# relay_board.net
KiCad netlist of a schematic drawn in EAGLE
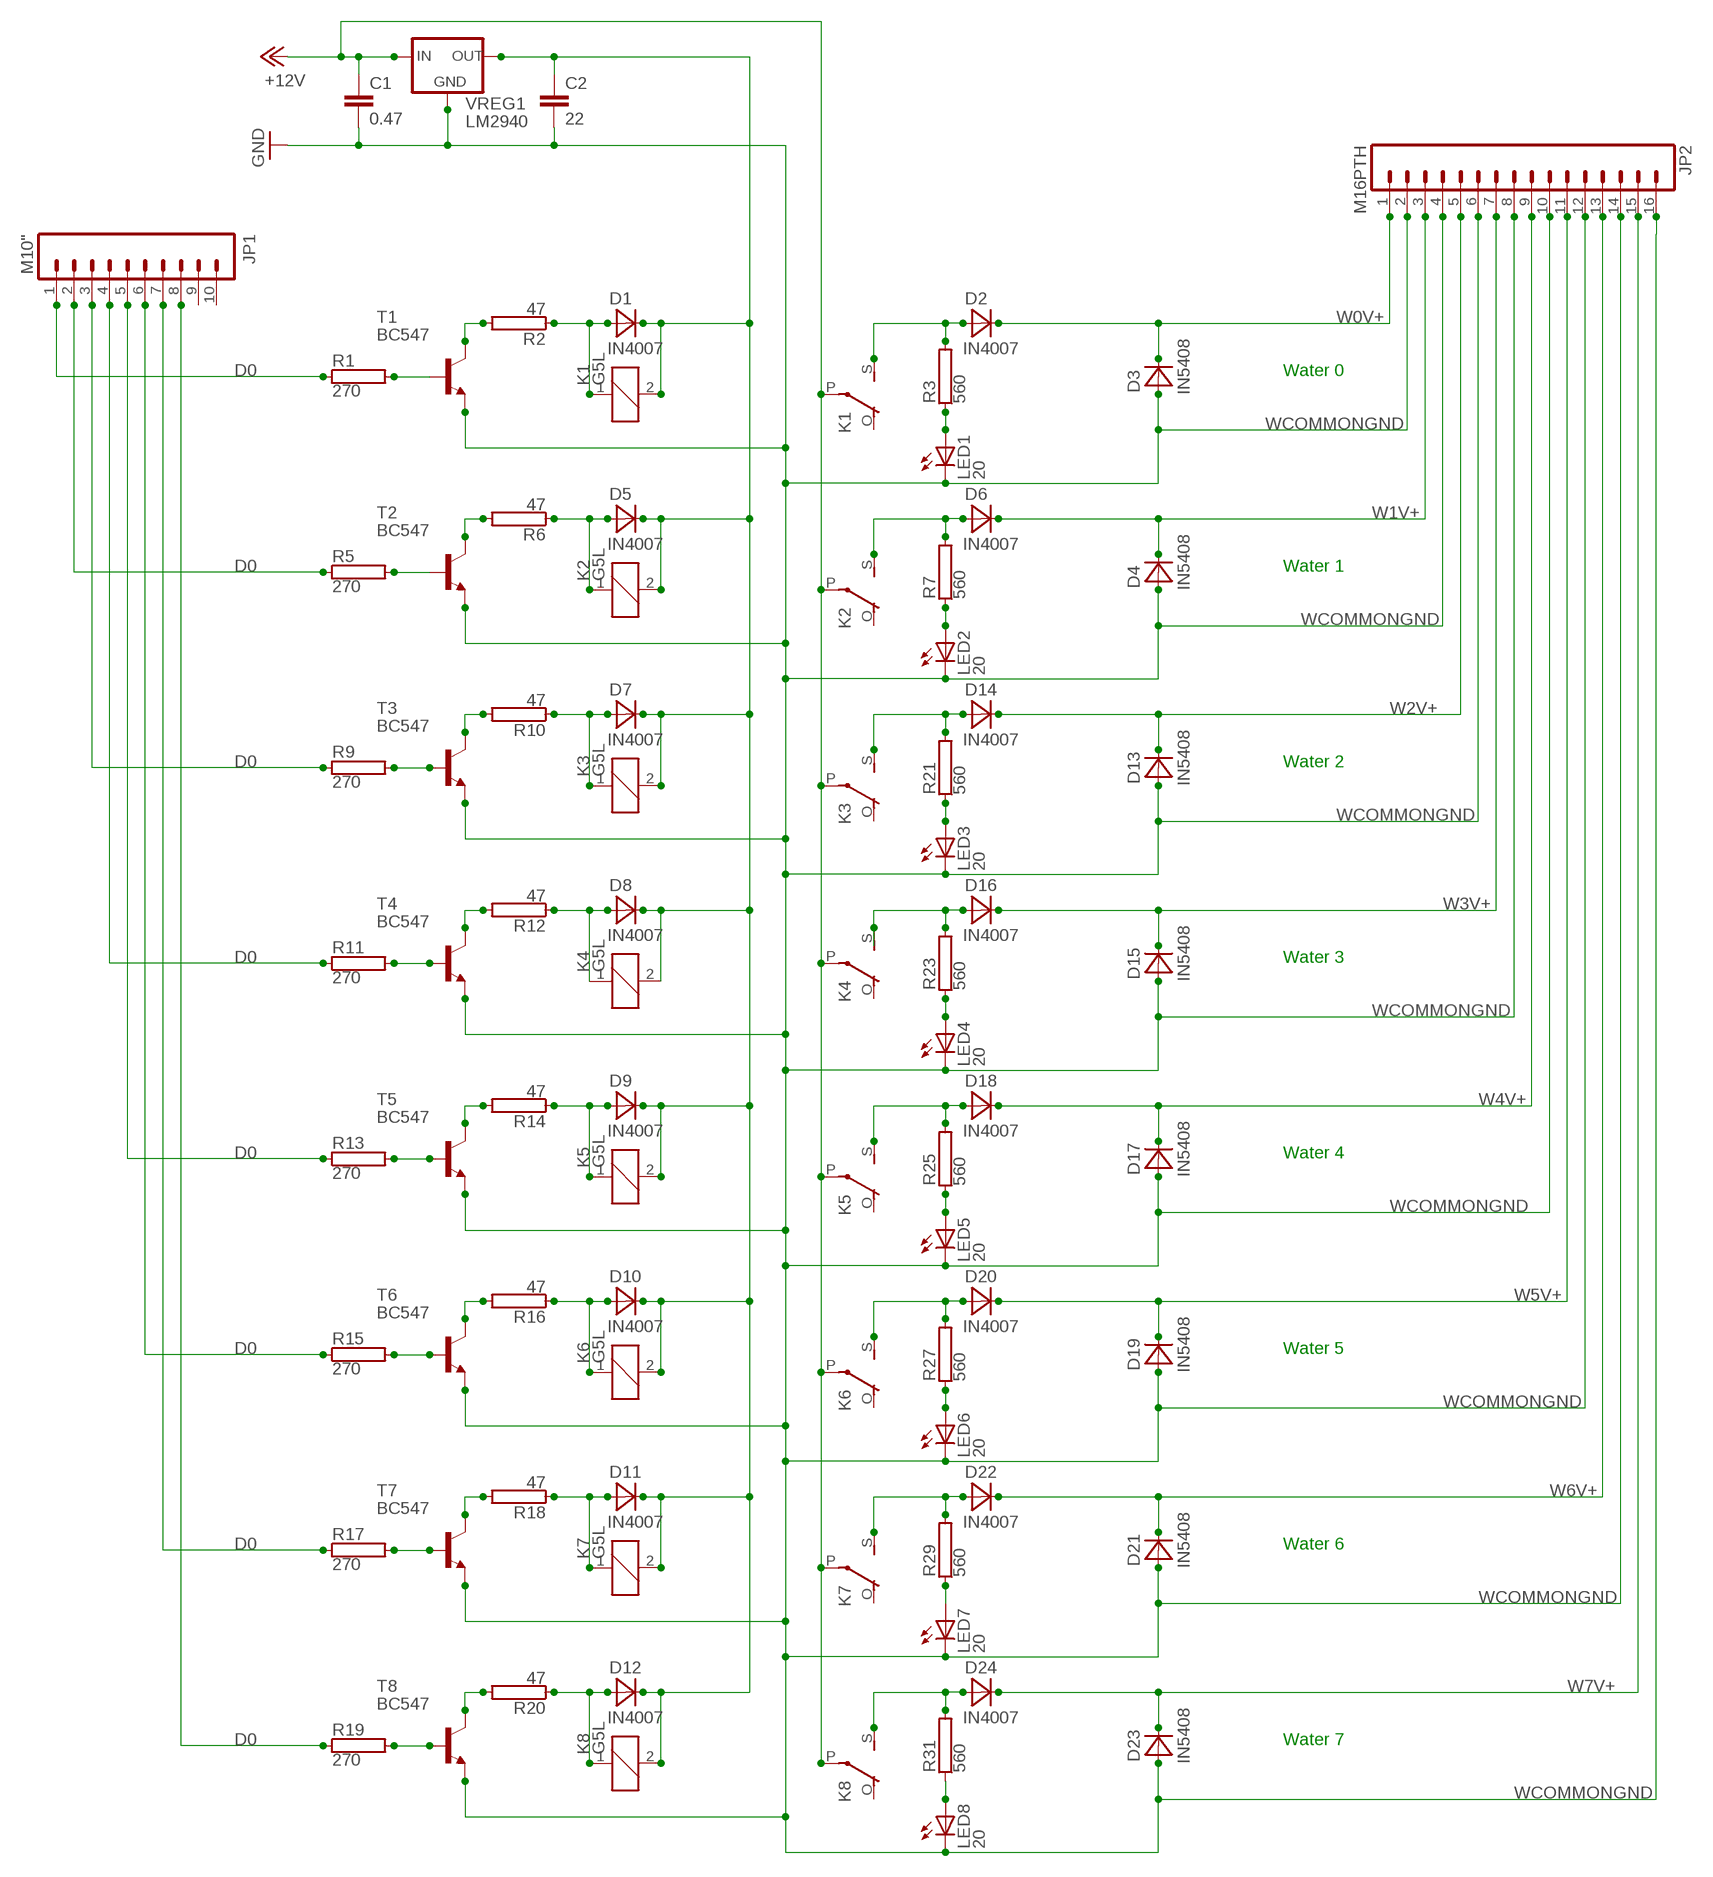
[diagram p0: schematic, sheet 1]

(export (version "E")
  (design (tool "Eeschema 10.0.6"))
  (components
    (comp (ref "C1")
      (value "0.47")
      (footprint "eagle-import:C2.5-3")
      (libsource (lib "eagle-import") (part "C2,5-3"))
    )
    (comp (ref "C2")
      (value "22")
      (footprint "eagle-import:C2.5-3")
      (libsource (lib "eagle-import") (part "C2,5-3"))
    )
    (comp (ref "D1")
      (value "IN4007")
      (footprint "eagle-import:DO41-10")
      (libsource (lib "eagle-import") (part "IN4007"))
    )
    (comp (ref "D2")
      (value "IN4007")
      (footprint "eagle-import:DO41-10")
      (libsource (lib "eagle-import") (part "IN4007"))
    )
    (comp (ref "D3")
      (value "IN5408")
      (footprint "eagle-import:DO41-10")
      (libsource (lib "eagle-import") (part "IN5408"))
    )
    (comp (ref "D4")
      (value "IN5408")
      (footprint "eagle-import:DO41-10")
      (libsource (lib "eagle-import") (part "IN5408"))
    )
    (comp (ref "D5")
      (value "IN4007")
      (footprint "eagle-import:DO41-10")
      (libsource (lib "eagle-import") (part "IN4007"))
    )
    (comp (ref "D6")
      (value "IN4007")
      (footprint "eagle-import:DO41-10")
      (libsource (lib "eagle-import") (part "IN4007"))
    )
    (comp (ref "D7")
      (value "IN4007")
      (footprint "eagle-import:DO41-10")
      (libsource (lib "eagle-import") (part "IN4007"))
    )
    (comp (ref "D8")
      (value "IN4007")
      (footprint "eagle-import:DO41-10")
      (libsource (lib "eagle-import") (part "IN4007"))
    )
    (comp (ref "D9")
      (value "IN4007")
      (footprint "eagle-import:DO41-10")
      (libsource (lib "eagle-import") (part "IN4007"))
    )
    (comp (ref "D10")
      (value "IN4007")
      (footprint "eagle-import:DO41-10")
      (libsource (lib "eagle-import") (part "IN4007"))
    )
    (comp (ref "D11")
      (value "IN4007")
      (footprint "eagle-import:DO41-10")
      (libsource (lib "eagle-import") (part "IN4007"))
    )
    (comp (ref "D12")
      (value "IN4007")
      (footprint "eagle-import:DO41-10")
      (libsource (lib "eagle-import") (part "IN4007"))
    )
    (comp (ref "D13")
      (value "IN5408")
      (footprint "eagle-import:DO41-10")
      (libsource (lib "eagle-import") (part "IN5408"))
    )
    (comp (ref "D14")
      (value "IN4007")
      (footprint "eagle-import:DO41-10")
      (libsource (lib "eagle-import") (part "IN4007"))
    )
    (comp (ref "D15")
      (value "IN5408")
      (footprint "eagle-import:DO41-10")
      (libsource (lib "eagle-import") (part "IN5408"))
    )
    (comp (ref "D16")
      (value "IN4007")
      (footprint "eagle-import:DO41-10")
      (libsource (lib "eagle-import") (part "IN4007"))
    )
    (comp (ref "D17")
      (value "IN5408")
      (footprint "eagle-import:DO41-10")
      (libsource (lib "eagle-import") (part "IN5408"))
    )
    (comp (ref "D18")
      (value "IN4007")
      (footprint "eagle-import:DO41-10")
      (libsource (lib "eagle-import") (part "IN4007"))
    )
    (comp (ref "D19")
      (value "IN5408")
      (footprint "eagle-import:DO41-10")
      (libsource (lib "eagle-import") (part "IN5408"))
    )
    (comp (ref "D20")
      (value "IN4007")
      (footprint "eagle-import:DO41-10")
      (libsource (lib "eagle-import") (part "IN4007"))
    )
    (comp (ref "D21")
      (value "IN5408")
      (footprint "eagle-import:DO41-10")
      (libsource (lib "eagle-import") (part "IN5408"))
    )
    (comp (ref "D22")
      (value "IN4007")
      (footprint "eagle-import:DO41-10")
      (libsource (lib "eagle-import") (part "IN4007"))
    )
    (comp (ref "D23")
      (value "IN5408")
      (footprint "eagle-import:DO41-10")
      (libsource (lib "eagle-import") (part "IN5408"))
    )
    (comp (ref "D24")
      (value "IN4007")
      (footprint "eagle-import:DO41-10")
      (libsource (lib "eagle-import") (part "IN4007"))
    )
    (comp (ref "JP1")
      (value "M10\"")
      (footprint "eagle-import:1X10")
      (libsource (lib "eagle-import") (part "M10{dblquote}"))
    )
    (comp (ref "JP2")
      (value "M16PTH")
      (footprint "eagle-import:1X16")
      (libsource (lib "eagle-import") (part "M16PTH"))
    )
    (comp (ref "K1")
      (value "G5L")
      (footprint "eagle-import:G5LE")
      (libsource (lib "eagle-import") (part "G5L"))
    )
    (comp (ref "K2")
      (value "G5L")
      (footprint "eagle-import:G5LE")
      (libsource (lib "eagle-import") (part "G5L"))
    )
    (comp (ref "K3")
      (value "G5L")
      (footprint "eagle-import:G5LE")
      (libsource (lib "eagle-import") (part "G5L"))
    )
    (comp (ref "K4")
      (value "G5L")
      (footprint "eagle-import:G5LE")
      (libsource (lib "eagle-import") (part "G5L"))
    )
    (comp (ref "K5")
      (value "G5L")
      (footprint "eagle-import:G5LE")
      (libsource (lib "eagle-import") (part "G5L"))
    )
    (comp (ref "K6")
      (value "G5L")
      (footprint "eagle-import:G5LE")
      (libsource (lib "eagle-import") (part "G5L"))
    )
    (comp (ref "K7")
      (value "G5L")
      (footprint "eagle-import:G5LE")
      (libsource (lib "eagle-import") (part "G5L"))
    )
    (comp (ref "K8")
      (value "G5L")
      (footprint "eagle-import:G5LE")
      (libsource (lib "eagle-import") (part "G5L"))
    )
    (comp (ref "LED1")
      (value "20")
      (footprint "eagle-import:LED5MM")
      (libsource (lib "eagle-import") (part "LED5MM"))
    )
    (comp (ref "LED2")
      (value "20")
      (footprint "eagle-import:LED5MM")
      (libsource (lib "eagle-import") (part "LED5MM"))
    )
    (comp (ref "LED3")
      (value "20")
      (footprint "eagle-import:LED5MM")
      (libsource (lib "eagle-import") (part "LED5MM"))
    )
    (comp (ref "LED4")
      (value "20")
      (footprint "eagle-import:LED5MM")
      (libsource (lib "eagle-import") (part "LED5MM"))
    )
    (comp (ref "LED5")
      (value "20")
      (footprint "eagle-import:LED5MM")
      (libsource (lib "eagle-import") (part "LED5MM"))
    )
    (comp (ref "LED6")
      (value "20")
      (footprint "eagle-import:LED5MM")
      (libsource (lib "eagle-import") (part "LED5MM"))
    )
    (comp (ref "LED7")
      (value "20")
      (footprint "eagle-import:LED5MM")
      (libsource (lib "eagle-import") (part "LED5MM"))
    )
    (comp (ref "LED8")
      (value "20")
      (footprint "eagle-import:LED5MM")
      (libsource (lib "eagle-import") (part "LED5MM"))
    )
    (comp (ref "R1")
      (value "270")
      (footprint "eagle-import:AC01")
      (libsource (lib "eagle-import") (part "RAC01"))
    )
    (comp (ref "R2")
      (value "47")
      (footprint "eagle-import:AC01")
      (libsource (lib "eagle-import") (part "RAC01"))
    )
    (comp (ref "R3")
      (value "560")
      (footprint "eagle-import:AC01")
      (libsource (lib "eagle-import") (part "RAC01"))
    )
    (comp (ref "R5")
      (value "270")
      (footprint "eagle-import:AC01")
      (libsource (lib "eagle-import") (part "RAC01"))
    )
    (comp (ref "R6")
      (value "47")
      (footprint "eagle-import:AC01")
      (libsource (lib "eagle-import") (part "RAC01"))
    )
    (comp (ref "R7")
      (value "560")
      (footprint "eagle-import:AC01")
      (libsource (lib "eagle-import") (part "RAC01"))
    )
    (comp (ref "R9")
      (value "270")
      (footprint "eagle-import:AC01")
      (libsource (lib "eagle-import") (part "RAC01"))
    )
    (comp (ref "R10")
      (value "47")
      (footprint "eagle-import:AC01")
      (libsource (lib "eagle-import") (part "RAC01"))
    )
    (comp (ref "R11")
      (value "270")
      (footprint "eagle-import:AC01")
      (libsource (lib "eagle-import") (part "RAC01"))
    )
    (comp (ref "R12")
      (value "47")
      (footprint "eagle-import:AC01")
      (libsource (lib "eagle-import") (part "RAC01"))
    )
    (comp (ref "R13")
      (value "270")
      (footprint "eagle-import:AC01")
      (libsource (lib "eagle-import") (part "RAC01"))
    )
    (comp (ref "R14")
      (value "47")
      (footprint "eagle-import:AC01")
      (libsource (lib "eagle-import") (part "RAC01"))
    )
    (comp (ref "R15")
      (value "270")
      (footprint "eagle-import:AC01")
      (libsource (lib "eagle-import") (part "RAC01"))
    )
    (comp (ref "R16")
      (value "47")
      (footprint "eagle-import:AC01")
      (libsource (lib "eagle-import") (part "RAC01"))
    )
    (comp (ref "R17")
      (value "270")
      (footprint "eagle-import:AC01")
      (libsource (lib "eagle-import") (part "RAC01"))
    )
    (comp (ref "R18")
      (value "47")
      (footprint "eagle-import:AC01")
      (libsource (lib "eagle-import") (part "RAC01"))
    )
    (comp (ref "R19")
      (value "270")
      (footprint "eagle-import:AC01")
      (libsource (lib "eagle-import") (part "RAC01"))
    )
    (comp (ref "R20")
      (value "47")
      (footprint "eagle-import:AC01")
      (libsource (lib "eagle-import") (part "RAC01"))
    )
    (comp (ref "R21")
      (value "560")
      (footprint "eagle-import:AC01")
      (libsource (lib "eagle-import") (part "RAC01"))
    )
    (comp (ref "R23")
      (value "560")
      (footprint "eagle-import:AC01")
      (libsource (lib "eagle-import") (part "RAC01"))
    )
    (comp (ref "R25")
      (value "560")
      (footprint "eagle-import:AC01")
      (libsource (lib "eagle-import") (part "RAC01"))
    )
    (comp (ref "R27")
      (value "560")
      (footprint "eagle-import:AC01")
      (libsource (lib "eagle-import") (part "RAC01"))
    )
    (comp (ref "R29")
      (value "560")
      (footprint "eagle-import:AC01")
      (libsource (lib "eagle-import") (part "RAC01"))
    )
    (comp (ref "R31")
      (value "560")
      (footprint "eagle-import:AC01")
      (libsource (lib "eagle-import") (part "RAC01"))
    )
    (comp (ref "T1")
      (value "BC547")
      (footprint "eagle-import:TO92")
      (libsource (lib "eagle-import") (part "BC547"))
    )
    (comp (ref "T2")
      (value "BC547")
      (footprint "eagle-import:TO92")
      (libsource (lib "eagle-import") (part "BC547"))
    )
    (comp (ref "T3")
      (value "BC547")
      (footprint "eagle-import:TO92")
      (libsource (lib "eagle-import") (part "BC547"))
    )
    (comp (ref "T4")
      (value "BC547")
      (footprint "eagle-import:TO92")
      (libsource (lib "eagle-import") (part "BC547"))
    )
    (comp (ref "T5")
      (value "BC547")
      (footprint "eagle-import:TO92")
      (libsource (lib "eagle-import") (part "BC547"))
    )
    (comp (ref "T6")
      (value "BC547")
      (footprint "eagle-import:TO92")
      (libsource (lib "eagle-import") (part "BC547"))
    )
    (comp (ref "T7")
      (value "BC547")
      (footprint "eagle-import:TO92")
      (libsource (lib "eagle-import") (part "BC547"))
    )
    (comp (ref "T8")
      (value "BC547")
      (footprint "eagle-import:TO92")
      (libsource (lib "eagle-import") (part "BC547"))
    )
    (comp (ref "VREG1")
      (value "LM2940")
      (footprint "eagle-import:78XXL")
      (libsource (lib "eagle-import") (part "LM2940"))
    )
  )
  (nets
    (net (code "1") (name "+12V") (class "Default")
      (node (ref "C1") (pin "1") (pinfunction "1_1") (pintype "passive"))
      (node (ref "K1") (pin "P") (pinfunction "P_P") (pintype "passive"))
      (node (ref "K2") (pin "P") (pinfunction "P_P") (pintype "passive"))
      (node (ref "K3") (pin "P") (pinfunction "P_P") (pintype "passive"))
      (node (ref "K4") (pin "P") (pinfunction "P_P") (pintype "passive"))
      (node (ref "K5") (pin "P") (pinfunction "P_P") (pintype "passive"))
      (node (ref "K6") (pin "P") (pinfunction "P_P") (pintype "passive"))
      (node (ref "K7") (pin "P") (pinfunction "P_P") (pintype "passive"))
      (node (ref "K8") (pin "P") (pinfunction "P_P") (pintype "passive"))
      (node (ref "VREG1") (pin "IN") (pinfunction "IN_IN") (pintype "input"))
    )
    (net (code "2") (name "/D0") (class "Default")
      (node (ref "JP1") (pin "1") (pinfunction "1_1") (pintype "passive"))
      (node (ref "JP1") (pin "2") (pinfunction "2_2") (pintype "passive"))
      (node (ref "JP1") (pin "3") (pinfunction "3_3") (pintype "passive"))
      (node (ref "JP1") (pin "4") (pinfunction "4_4") (pintype "passive"))
      (node (ref "JP1") (pin "5") (pinfunction "5_5") (pintype "passive"))
      (node (ref "JP1") (pin "6") (pinfunction "6_6") (pintype "passive"))
      (node (ref "JP1") (pin "7") (pinfunction "7_7") (pintype "passive"))
      (node (ref "JP1") (pin "8") (pinfunction "8_8") (pintype "passive"))
      (node (ref "R1") (pin "1") (pinfunction "1_1") (pintype "passive"))
      (node (ref "R11") (pin "1") (pinfunction "1_1") (pintype "passive"))
      (node (ref "R13") (pin "1") (pinfunction "1_1") (pintype "passive"))
      (node (ref "R15") (pin "1") (pinfunction "1_1") (pintype "passive"))
      (node (ref "R17") (pin "1") (pinfunction "1_1") (pintype "passive"))
      (node (ref "R19") (pin "1") (pinfunction "1_1") (pintype "passive"))
      (node (ref "R5") (pin "1") (pinfunction "1_1") (pintype "passive"))
      (node (ref "R9") (pin "1") (pinfunction "1_1") (pintype "passive"))
    )
    (net (code "3") (name "/W0V+") (class "Default")
      (node (ref "D2") (pin "C") (pinfunction "C_C") (pintype "passive"))
      (node (ref "D3") (pin "C") (pinfunction "C_C") (pintype "passive"))
      (node (ref "JP2") (pin "1") (pinfunction "1_1") (pintype "passive"))
    )
    (net (code "4") (name "/W1V+") (class "Default")
      (node (ref "D4") (pin "C") (pinfunction "C_C") (pintype "passive"))
      (node (ref "D6") (pin "C") (pinfunction "C_C") (pintype "passive"))
      (node (ref "JP2") (pin "3") (pinfunction "3_3") (pintype "passive"))
    )
    (net (code "5") (name "/W2V+") (class "Default")
      (node (ref "D13") (pin "C") (pinfunction "C_C") (pintype "passive"))
      (node (ref "D14") (pin "C") (pinfunction "C_C") (pintype "passive"))
      (node (ref "JP2") (pin "5") (pinfunction "5_5") (pintype "passive"))
    )
    (net (code "6") (name "/W3V+") (class "Default")
      (node (ref "D15") (pin "C") (pinfunction "C_C") (pintype "passive"))
      (node (ref "D16") (pin "C") (pinfunction "C_C") (pintype "passive"))
      (node (ref "JP2") (pin "7") (pinfunction "7_7") (pintype "passive"))
    )
    (net (code "7") (name "/W4V+") (class "Default")
      (node (ref "D17") (pin "C") (pinfunction "C_C") (pintype "passive"))
      (node (ref "D18") (pin "C") (pinfunction "C_C") (pintype "passive"))
      (node (ref "JP2") (pin "9") (pinfunction "9_9") (pintype "passive"))
    )
    (net (code "8") (name "/W5V+") (class "Default")
      (node (ref "D19") (pin "C") (pinfunction "C_C") (pintype "passive"))
      (node (ref "D20") (pin "C") (pinfunction "C_C") (pintype "passive"))
      (node (ref "JP2") (pin "11") (pinfunction "11_11") (pintype "passive"))
    )
    (net (code "9") (name "/W6V+") (class "Default")
      (node (ref "D21") (pin "C") (pinfunction "C_C") (pintype "passive"))
      (node (ref "D22") (pin "C") (pinfunction "C_C") (pintype "passive"))
      (node (ref "JP2") (pin "13") (pinfunction "13_13") (pintype "passive"))
    )
    (net (code "10") (name "/W7V+") (class "Default")
      (node (ref "D23") (pin "C") (pinfunction "C_C") (pintype "passive"))
      (node (ref "D24") (pin "C") (pinfunction "C_C") (pintype "passive"))
      (node (ref "JP2") (pin "15") (pinfunction "15_15") (pintype "passive"))
    )
    (net (code "11") (name "GND") (class "Default")
      (node (ref "C1") (pin "2") (pinfunction "2_2") (pintype "passive"))
      (node (ref "C2") (pin "2") (pinfunction "2_2") (pintype "passive"))
      (node (ref "D13") (pin "A") (pinfunction "A_A") (pintype "passive"))
      (node (ref "D15") (pin "A") (pinfunction "A_A") (pintype "passive"))
      (node (ref "D17") (pin "A") (pinfunction "A_A") (pintype "passive"))
      (node (ref "D19") (pin "A") (pinfunction "A_A") (pintype "passive"))
      (node (ref "D21") (pin "A") (pinfunction "A_A") (pintype "passive"))
      (node (ref "D23") (pin "A") (pinfunction "A_A") (pintype "passive"))
      (node (ref "D3") (pin "A") (pinfunction "A_A") (pintype "passive"))
      (node (ref "D4") (pin "A") (pinfunction "A_A") (pintype "passive"))
      (node (ref "JP2") (pin "10") (pinfunction "10_10") (pintype "passive"))
      (node (ref "JP2") (pin "12") (pinfunction "12_12") (pintype "passive"))
      (node (ref "JP2") (pin "14") (pinfunction "14_14") (pintype "passive"))
      (node (ref "JP2") (pin "16") (pinfunction "16_16") (pintype "passive"))
      (node (ref "JP2") (pin "2") (pinfunction "2_2") (pintype "passive"))
      (node (ref "JP2") (pin "4") (pinfunction "4_4") (pintype "passive"))
      (node (ref "JP2") (pin "6") (pinfunction "6_6") (pintype "passive"))
      (node (ref "JP2") (pin "8") (pinfunction "8_8") (pintype "passive"))
      (node (ref "LED1") (pin "K") (pinfunction "C_K") (pintype "passive"))
      (node (ref "LED2") (pin "K") (pinfunction "C_K") (pintype "passive"))
      (node (ref "LED3") (pin "K") (pinfunction "C_K") (pintype "passive"))
      (node (ref "LED4") (pin "K") (pinfunction "C_K") (pintype "passive"))
      (node (ref "LED5") (pin "K") (pinfunction "C_K") (pintype "passive"))
      (node (ref "LED6") (pin "K") (pinfunction "C_K") (pintype "passive"))
      (node (ref "LED7") (pin "K") (pinfunction "C_K") (pintype "passive"))
      (node (ref "LED8") (pin "K") (pinfunction "C_K") (pintype "passive"))
      (node (ref "T1") (pin "1") (pinfunction "E_1") (pintype "passive"))
      (node (ref "T2") (pin "1") (pinfunction "E_1") (pintype "passive"))
      (node (ref "T3") (pin "1") (pinfunction "E_1") (pintype "passive"))
      (node (ref "T4") (pin "1") (pinfunction "E_1") (pintype "passive"))
      (node (ref "T5") (pin "1") (pinfunction "E_1") (pintype "passive"))
      (node (ref "T6") (pin "1") (pinfunction "E_1") (pintype "passive"))
      (node (ref "T7") (pin "1") (pinfunction "E_1") (pintype "passive"))
      (node (ref "T8") (pin "1") (pinfunction "E_1") (pintype "passive"))
      (node (ref "VREG1") (pin "GND") (pinfunction "GND_GND") (pintype "input"))
    )
    (net (code "12") (name "Net-(C2-Pad1)") (class "Default")
      (node (ref "C2") (pin "1") (pinfunction "1_1") (pintype "passive"))
      (node (ref "D1") (pin "C") (pinfunction "C_C") (pintype "passive"))
      (node (ref "D10") (pin "C") (pinfunction "C_C") (pintype "passive"))
      (node (ref "D11") (pin "C") (pinfunction "C_C") (pintype "passive"))
      (node (ref "D12") (pin "C") (pinfunction "C_C") (pintype "passive"))
      (node (ref "D5") (pin "C") (pinfunction "C_C") (pintype "passive"))
      (node (ref "D7") (pin "C") (pinfunction "C_C") (pintype "passive"))
      (node (ref "D8") (pin "C") (pinfunction "C_C") (pintype "passive"))
      (node (ref "D9") (pin "C") (pinfunction "C_C") (pintype "passive"))
      (node (ref "K1") (pin "2") (pinfunction "2_2") (pintype "passive"))
      (node (ref "K2") (pin "2") (pinfunction "2_2") (pintype "passive"))
      (node (ref "K3") (pin "2") (pinfunction "2_2") (pintype "passive"))
      (node (ref "K4") (pin "2") (pinfunction "2_2") (pintype "passive"))
      (node (ref "K5") (pin "2") (pinfunction "2_2") (pintype "passive"))
      (node (ref "K6") (pin "2") (pinfunction "2_2") (pintype "passive"))
      (node (ref "K7") (pin "2") (pinfunction "2_2") (pintype "passive"))
      (node (ref "K8") (pin "2") (pinfunction "2_2") (pintype "passive"))
      (node (ref "VREG1") (pin "OUT") (pinfunction "OUT_OUT") (pintype "passive"))
    )
    (net (code "13") (name "Net-(D1-PadA)") (class "Default")
      (node (ref "D1") (pin "A") (pinfunction "A_A") (pintype "passive"))
      (node (ref "K1") (pin "1") (pinfunction "1_1") (pintype "passive"))
      (node (ref "R2") (pin "1") (pinfunction "1_1") (pintype "passive"))
    )
    (net (code "14") (name "Net-(D2-PadA)") (class "Default")
      (node (ref "D2") (pin "A") (pinfunction "A_A") (pintype "passive"))
      (node (ref "K1") (pin "S") (pinfunction "S_S") (pintype "passive"))
      (node (ref "R3") (pin "2") (pinfunction "2_2") (pintype "passive"))
    )
    (net (code "15") (name "Net-(D5-PadA)") (class "Default")
      (node (ref "D5") (pin "A") (pinfunction "A_A") (pintype "passive"))
      (node (ref "K2") (pin "1") (pinfunction "1_1") (pintype "passive"))
      (node (ref "R6") (pin "1") (pinfunction "1_1") (pintype "passive"))
    )
    (net (code "16") (name "Net-(D6-PadA)") (class "Default")
      (node (ref "D6") (pin "A") (pinfunction "A_A") (pintype "passive"))
      (node (ref "K2") (pin "S") (pinfunction "S_S") (pintype "passive"))
      (node (ref "R7") (pin "2") (pinfunction "2_2") (pintype "passive"))
    )
    (net (code "17") (name "Net-(D7-PadA)") (class "Default")
      (node (ref "D7") (pin "A") (pinfunction "A_A") (pintype "passive"))
      (node (ref "K3") (pin "1") (pinfunction "1_1") (pintype "passive"))
      (node (ref "R10") (pin "1") (pinfunction "1_1") (pintype "passive"))
    )
    (net (code "18") (name "Net-(D8-PadA)") (class "Default")
      (node (ref "D8") (pin "A") (pinfunction "A_A") (pintype "passive"))
      (node (ref "K4") (pin "1") (pinfunction "1_1") (pintype "passive"))
      (node (ref "R12") (pin "1") (pinfunction "1_1") (pintype "passive"))
    )
    (net (code "19") (name "Net-(D9-PadA)") (class "Default")
      (node (ref "D9") (pin "A") (pinfunction "A_A") (pintype "passive"))
      (node (ref "K5") (pin "1") (pinfunction "1_1") (pintype "passive"))
      (node (ref "R14") (pin "1") (pinfunction "1_1") (pintype "passive"))
    )
    (net (code "20") (name "Net-(D10-PadA)") (class "Default")
      (node (ref "D10") (pin "A") (pinfunction "A_A") (pintype "passive"))
      (node (ref "K6") (pin "1") (pinfunction "1_1") (pintype "passive"))
      (node (ref "R16") (pin "1") (pinfunction "1_1") (pintype "passive"))
    )
    (net (code "21") (name "Net-(D11-PadA)") (class "Default")
      (node (ref "D11") (pin "A") (pinfunction "A_A") (pintype "passive"))
      (node (ref "K7") (pin "1") (pinfunction "1_1") (pintype "passive"))
      (node (ref "R18") (pin "1") (pinfunction "1_1") (pintype "passive"))
    )
    (net (code "22") (name "Net-(D12-PadA)") (class "Default")
      (node (ref "D12") (pin "A") (pinfunction "A_A") (pintype "passive"))
      (node (ref "K8") (pin "1") (pinfunction "1_1") (pintype "passive"))
      (node (ref "R20") (pin "1") (pinfunction "1_1") (pintype "passive"))
    )
    (net (code "23") (name "Net-(D14-PadA)") (class "Default")
      (node (ref "D14") (pin "A") (pinfunction "A_A") (pintype "passive"))
      (node (ref "K3") (pin "S") (pinfunction "S_S") (pintype "passive"))
      (node (ref "R21") (pin "2") (pinfunction "2_2") (pintype "passive"))
    )
    (net (code "24") (name "Net-(D16-PadA)") (class "Default")
      (node (ref "D16") (pin "A") (pinfunction "A_A") (pintype "passive"))
      (node (ref "K4") (pin "S") (pinfunction "S_S") (pintype "passive"))
      (node (ref "R23") (pin "2") (pinfunction "2_2") (pintype "passive"))
    )
    (net (code "25") (name "Net-(D18-PadA)") (class "Default")
      (node (ref "D18") (pin "A") (pinfunction "A_A") (pintype "passive"))
      (node (ref "K5") (pin "S") (pinfunction "S_S") (pintype "passive"))
      (node (ref "R25") (pin "2") (pinfunction "2_2") (pintype "passive"))
    )
    (net (code "26") (name "Net-(D20-PadA)") (class "Default")
      (node (ref "D20") (pin "A") (pinfunction "A_A") (pintype "passive"))
      (node (ref "K6") (pin "S") (pinfunction "S_S") (pintype "passive"))
      (node (ref "R27") (pin "2") (pinfunction "2_2") (pintype "passive"))
    )
    (net (code "27") (name "Net-(D22-PadA)") (class "Default")
      (node (ref "D22") (pin "A") (pinfunction "A_A") (pintype "passive"))
      (node (ref "K7") (pin "S") (pinfunction "S_S") (pintype "passive"))
      (node (ref "R29") (pin "2") (pinfunction "2_2") (pintype "passive"))
    )
    (net (code "28") (name "Net-(D24-PadA)") (class "Default")
      (node (ref "D24") (pin "A") (pinfunction "A_A") (pintype "passive"))
      (node (ref "K8") (pin "S") (pinfunction "S_S") (pintype "passive"))
      (node (ref "R31") (pin "2") (pinfunction "2_2") (pintype "passive"))
    )
    (net (code "29") (name "Net-(LED1-PadA)") (class "Default")
      (node (ref "LED1") (pin "A") (pinfunction "A_A") (pintype "passive"))
      (node (ref "R3") (pin "1") (pinfunction "1_1") (pintype "passive"))
    )
    (net (code "30") (name "Net-(LED2-PadA)") (class "Default")
      (node (ref "LED2") (pin "A") (pinfunction "A_A") (pintype "passive"))
      (node (ref "R7") (pin "1") (pinfunction "1_1") (pintype "passive"))
    )
    (net (code "31") (name "Net-(LED3-PadA)") (class "Default")
      (node (ref "LED3") (pin "A") (pinfunction "A_A") (pintype "passive"))
      (node (ref "R21") (pin "1") (pinfunction "1_1") (pintype "passive"))
    )
    (net (code "32") (name "Net-(LED4-PadA)") (class "Default")
      (node (ref "LED4") (pin "A") (pinfunction "A_A") (pintype "passive"))
      (node (ref "R23") (pin "1") (pinfunction "1_1") (pintype "passive"))
    )
    (net (code "33") (name "Net-(LED5-PadA)") (class "Default")
      (node (ref "LED5") (pin "A") (pinfunction "A_A") (pintype "passive"))
      (node (ref "R25") (pin "1") (pinfunction "1_1") (pintype "passive"))
    )
    (net (code "34") (name "Net-(LED6-PadA)") (class "Default")
      (node (ref "LED6") (pin "A") (pinfunction "A_A") (pintype "passive"))
      (node (ref "R27") (pin "1") (pinfunction "1_1") (pintype "passive"))
    )
    (net (code "35") (name "Net-(LED7-PadA)") (class "Default")
      (node (ref "LED7") (pin "A") (pinfunction "A_A") (pintype "passive"))
      (node (ref "R29") (pin "1") (pinfunction "1_1") (pintype "passive"))
    )
    (net (code "36") (name "Net-(LED8-PadA)") (class "Default")
      (node (ref "LED8") (pin "A") (pinfunction "A_A") (pintype "passive"))
      (node (ref "R31") (pin "1") (pinfunction "1_1") (pintype "passive"))
    )
    (net (code "37") (name "Net-(T1-B)") (class "Default")
      (node (ref "R1") (pin "2") (pinfunction "2_2") (pintype "passive"))
      (node (ref "T1") (pin "2") (pinfunction "B_2") (pintype "passive"))
    )
    (net (code "38") (name "Net-(T1-C)") (class "Default")
      (node (ref "R2") (pin "2") (pinfunction "2_2") (pintype "passive"))
      (node (ref "T1") (pin "3") (pinfunction "C_3") (pintype "passive"))
    )
    (net (code "39") (name "Net-(T2-B)") (class "Default")
      (node (ref "R5") (pin "2") (pinfunction "2_2") (pintype "passive"))
      (node (ref "T2") (pin "2") (pinfunction "B_2") (pintype "passive"))
    )
    (net (code "40") (name "Net-(T2-C)") (class "Default")
      (node (ref "R6") (pin "2") (pinfunction "2_2") (pintype "passive"))
      (node (ref "T2") (pin "3") (pinfunction "C_3") (pintype "passive"))
    )
    (net (code "41") (name "Net-(T3-B)") (class "Default")
      (node (ref "R9") (pin "2") (pinfunction "2_2") (pintype "passive"))
      (node (ref "T3") (pin "2") (pinfunction "B_2") (pintype "passive"))
    )
    (net (code "42") (name "Net-(T3-C)") (class "Default")
      (node (ref "R10") (pin "2") (pinfunction "2_2") (pintype "passive"))
      (node (ref "T3") (pin "3") (pinfunction "C_3") (pintype "passive"))
    )
    (net (code "43") (name "Net-(T4-B)") (class "Default")
      (node (ref "R11") (pin "2") (pinfunction "2_2") (pintype "passive"))
      (node (ref "T4") (pin "2") (pinfunction "B_2") (pintype "passive"))
    )
    (net (code "44") (name "Net-(T4-C)") (class "Default")
      (node (ref "R12") (pin "2") (pinfunction "2_2") (pintype "passive"))
      (node (ref "T4") (pin "3") (pinfunction "C_3") (pintype "passive"))
    )
    (net (code "45") (name "Net-(T5-B)") (class "Default")
      (node (ref "R13") (pin "2") (pinfunction "2_2") (pintype "passive"))
      (node (ref "T5") (pin "2") (pinfunction "B_2") (pintype "passive"))
    )
    (net (code "46") (name "Net-(T5-C)") (class "Default")
      (node (ref "R14") (pin "2") (pinfunction "2_2") (pintype "passive"))
      (node (ref "T5") (pin "3") (pinfunction "C_3") (pintype "passive"))
    )
    (net (code "47") (name "Net-(T6-B)") (class "Default")
      (node (ref "R15") (pin "2") (pinfunction "2_2") (pintype "passive"))
      (node (ref "T6") (pin "2") (pinfunction "B_2") (pintype "passive"))
    )
    (net (code "48") (name "Net-(T6-C)") (class "Default")
      (node (ref "R16") (pin "2") (pinfunction "2_2") (pintype "passive"))
      (node (ref "T6") (pin "3") (pinfunction "C_3") (pintype "passive"))
    )
    (net (code "49") (name "Net-(T7-B)") (class "Default")
      (node (ref "R17") (pin "2") (pinfunction "2_2") (pintype "passive"))
      (node (ref "T7") (pin "2") (pinfunction "B_2") (pintype "passive"))
    )
    (net (code "50") (name "Net-(T7-C)") (class "Default")
      (node (ref "R18") (pin "2") (pinfunction "2_2") (pintype "passive"))
      (node (ref "T7") (pin "3") (pinfunction "C_3") (pintype "passive"))
    )
    (net (code "51") (name "Net-(T8-B)") (class "Default")
      (node (ref "R19") (pin "2") (pinfunction "2_2") (pintype "passive"))
      (node (ref "T8") (pin "2") (pinfunction "B_2") (pintype "passive"))
    )
    (net (code "52") (name "Net-(T8-C)") (class "Default")
      (node (ref "R20") (pin "2") (pinfunction "2_2") (pintype "passive"))
      (node (ref "T8") (pin "3") (pinfunction "C_3") (pintype "passive"))
    )
    (net (code "53") (name "unconnected-(JP1-Pad9)") (class "Default")
      (node (ref "JP1") (pin "9") (pinfunction "9_9") (pintype "passive"))
    )
    (net (code "54") (name "unconnected-(JP1-Pad10)") (class "Default")
      (node (ref "JP1") (pin "10") (pinfunction "10_10") (pintype "passive"))
    )
    (net (code "55") (name "unconnected-(K1-PadO)") (class "Default")
      (node (ref "K1") (pin "O") (pinfunction "O_O") (pintype "passive"))
    )
    (net (code "56") (name "unconnected-(K2-PadO)") (class "Default")
      (node (ref "K2") (pin "O") (pinfunction "O_O") (pintype "passive"))
    )
    (net (code "57") (name "unconnected-(K3-PadO)") (class "Default")
      (node (ref "K3") (pin "O") (pinfunction "O_O") (pintype "passive"))
    )
    (net (code "58") (name "unconnected-(K4-PadO)") (class "Default")
      (node (ref "K4") (pin "O") (pinfunction "O_O") (pintype "passive"))
    )
    (net (code "59") (name "unconnected-(K5-PadO)") (class "Default")
      (node (ref "K5") (pin "O") (pinfunction "O_O") (pintype "passive"))
    )
    (net (code "60") (name "unconnected-(K6-PadO)") (class "Default")
      (node (ref "K6") (pin "O") (pinfunction "O_O") (pintype "passive"))
    )
    (net (code "61") (name "unconnected-(K7-PadO)") (class "Default")
      (node (ref "K7") (pin "O") (pinfunction "O_O") (pintype "passive"))
    )
    (net (code "62") (name "unconnected-(K8-PadO)") (class "Default")
      (node (ref "K8") (pin "O") (pinfunction "O_O") (pintype "passive"))
    )
  )
)
